# EasyEDA.net
KiCad netlist of a schematic drawn in EasyEDA
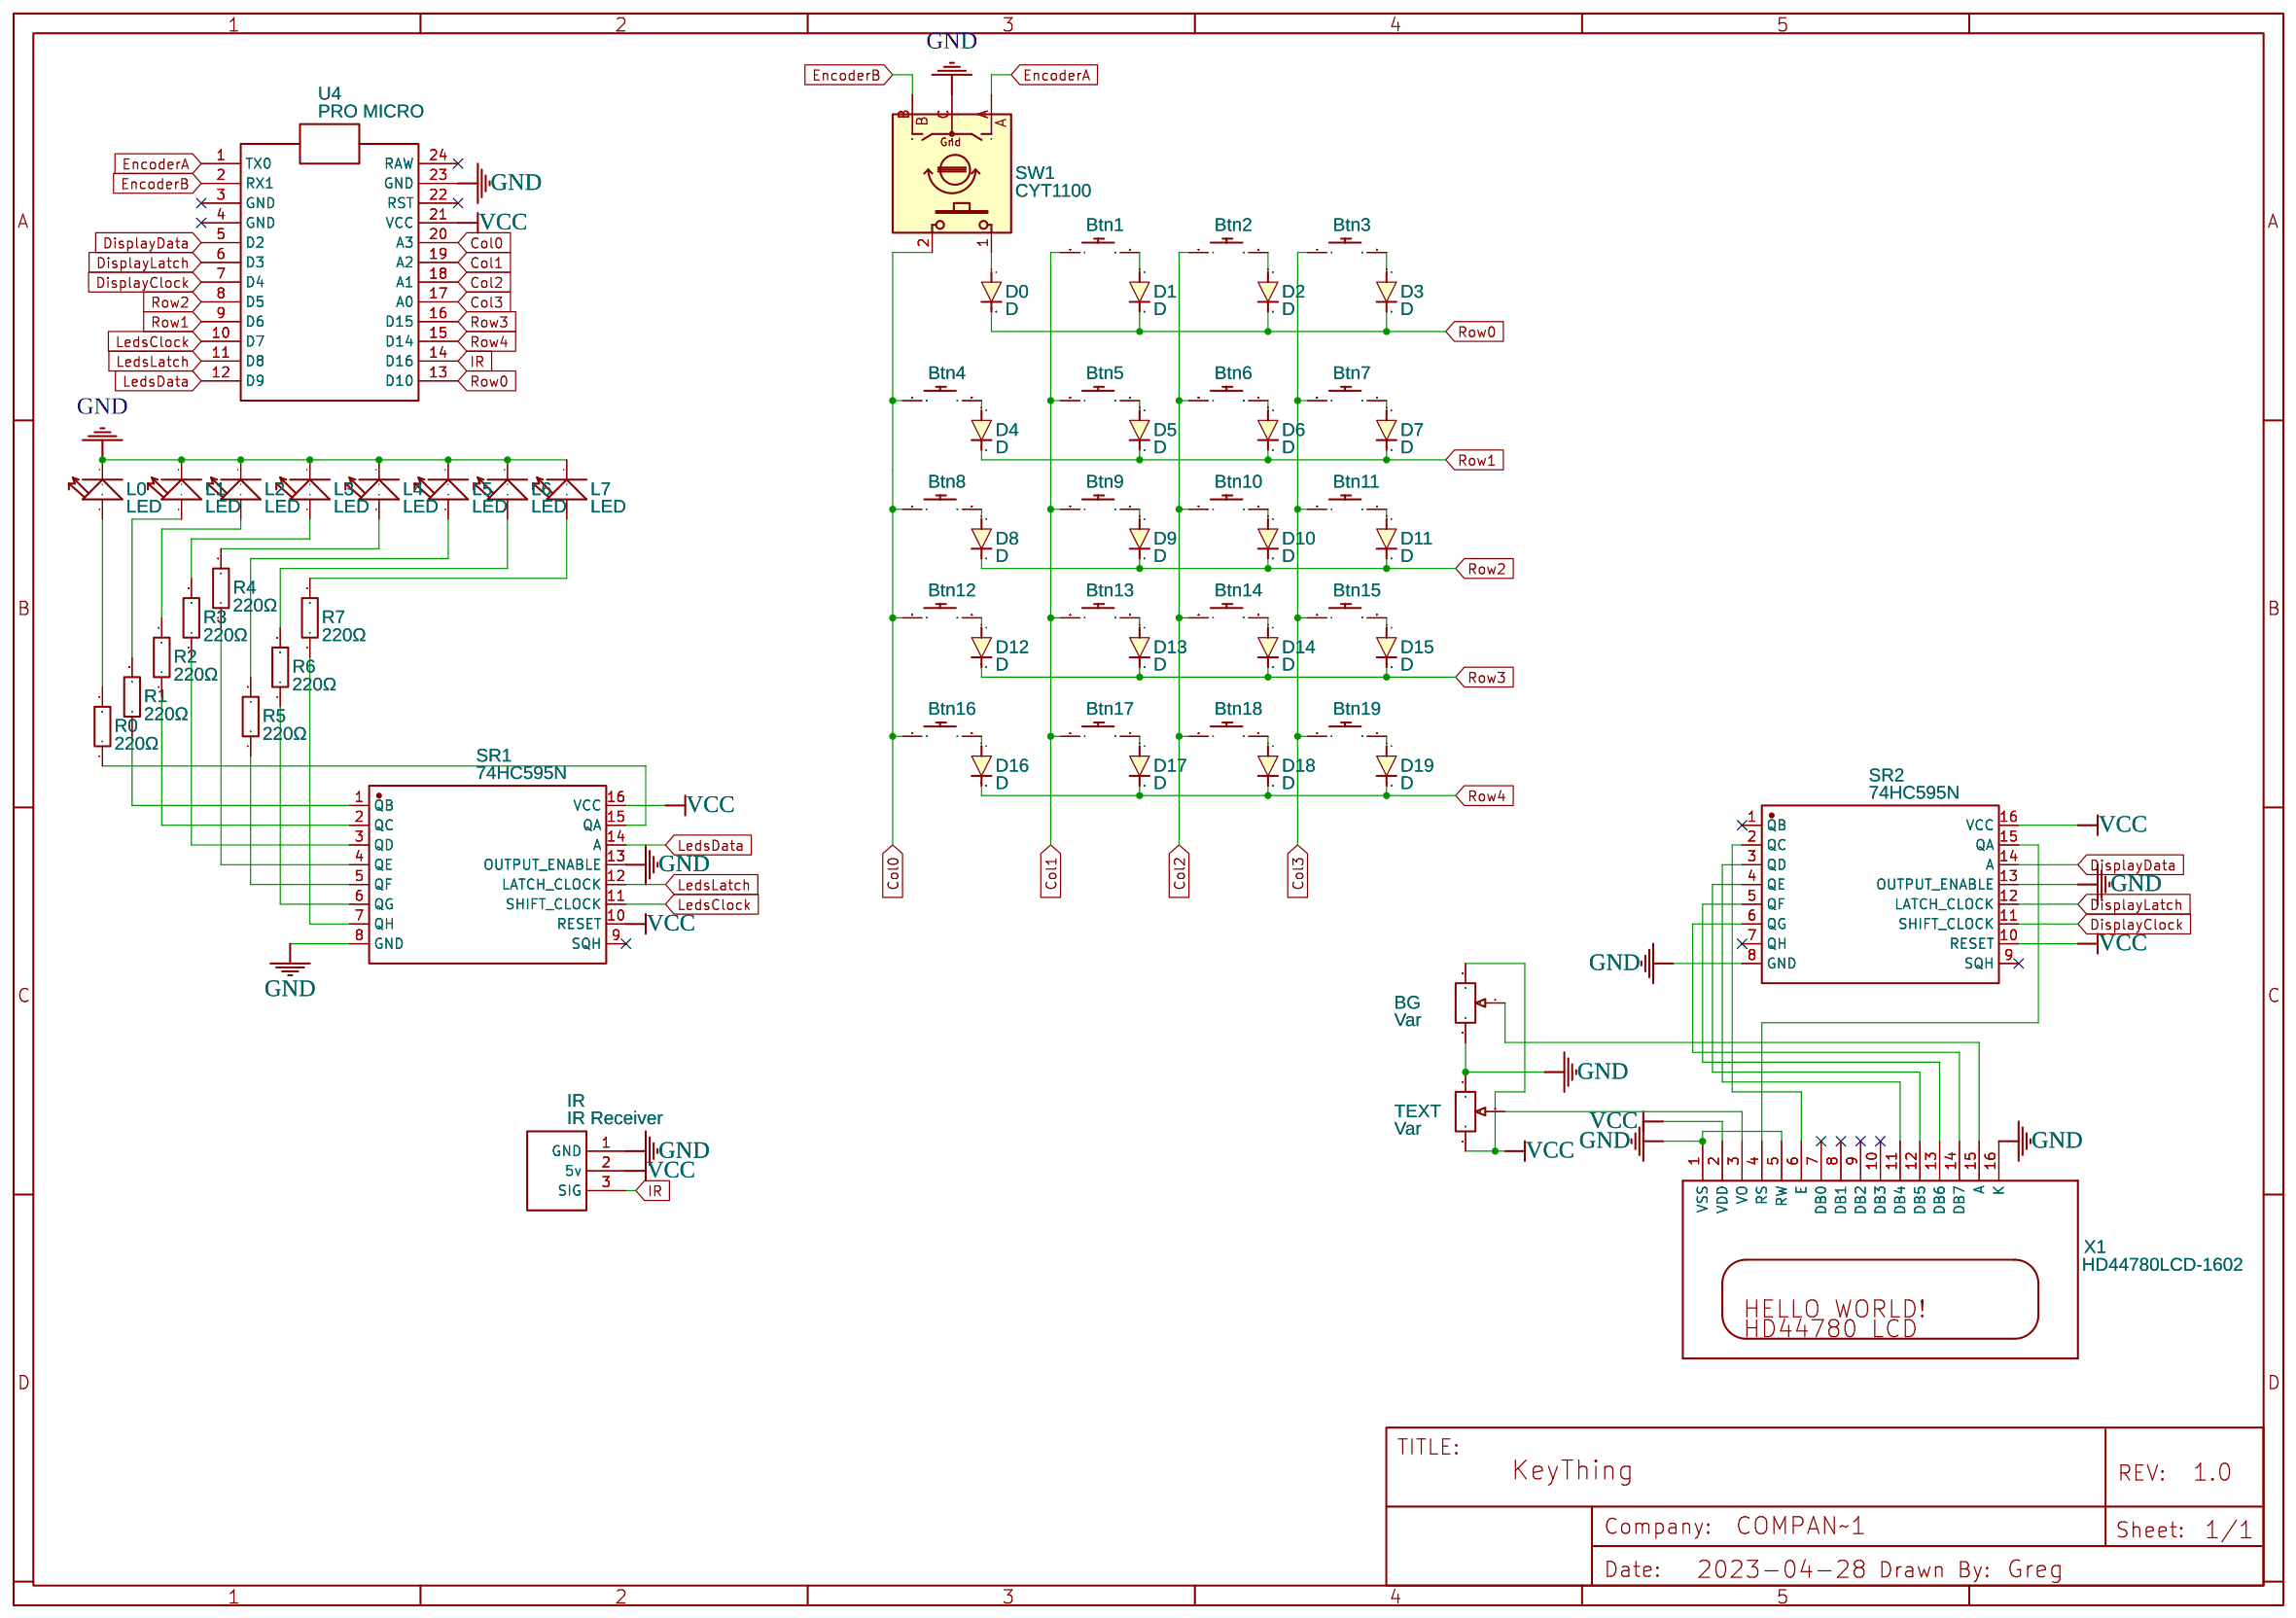
[diagram p0: schematic sheet]

(export (version "E")
  (design (tool "Eeschema 10.0.6"))
  (components
    (comp (ref "B1")
      (value "Btn1")
      (fields (field (name "BOM_Supplier Part") "264546125050"))
      (libsource (lib "") (part "Cherry MX"))
    )
    (comp (ref "B2")
      (value "Btn2")
      (fields (field (name "BOM_Supplier Part") "264546125050"))
      (libsource (lib "") (part "Cherry MX"))
    )
    (comp (ref "B3")
      (value "Btn3")
      (fields (field (name "BOM_Supplier Part") "264546125050"))
      (libsource (lib "") (part "Cherry MX"))
    )
    (comp (ref "B4")
      (value "Btn4")
      (fields (field (name "BOM_Supplier Part") "264546125050"))
      (libsource (lib "") (part "Cherry MX"))
    )
    (comp (ref "B5")
      (value "Btn5")
      (fields (field (name "BOM_Supplier Part") "264546125050"))
      (libsource (lib "") (part "Cherry MX"))
    )
    (comp (ref "B6")
      (value "Btn6")
      (fields (field (name "BOM_Supplier Part") "264546125050"))
      (libsource (lib "") (part "Cherry MX"))
    )
    (comp (ref "B7")
      (value "Btn7")
      (fields (field (name "BOM_Supplier Part") "264546125050"))
      (libsource (lib "") (part "Cherry MX"))
    )
    (comp (ref "B8")
      (value "Btn8")
      (fields (field (name "BOM_Supplier Part") "264546125050"))
      (libsource (lib "") (part "Cherry MX"))
    )
    (comp (ref "B9")
      (value "Btn9")
      (fields (field (name "BOM_Supplier Part") "264546125050"))
      (libsource (lib "") (part "Cherry MX"))
    )
    (comp (ref "B10")
      (value "Btn10")
      (fields (field (name "BOM_Supplier Part") "264546125050"))
      (libsource (lib "") (part "Cherry MX"))
    )
    (comp (ref "B11")
      (value "Btn11")
      (fields (field (name "BOM_Supplier Part") "264546125050"))
      (libsource (lib "") (part "Cherry MX"))
    )
    (comp (ref "B12")
      (value "Btn12")
      (fields (field (name "BOM_Supplier Part") "264546125050"))
      (libsource (lib "") (part "Cherry MX"))
    )
    (comp (ref "B13")
      (value "Btn13")
      (fields (field (name "BOM_Supplier Part") "264546125050"))
      (libsource (lib "") (part "Cherry MX"))
    )
    (comp (ref "B14")
      (value "Btn14")
      (fields (field (name "BOM_Supplier Part") "264546125050"))
      (libsource (lib "") (part "Cherry MX"))
    )
    (comp (ref "B15")
      (value "Btn15")
      (fields (field (name "BOM_Supplier Part") "264546125050"))
      (libsource (lib "") (part "Cherry MX"))
    )
    (comp (ref "B16")
      (value "Btn16")
      (fields (field (name "BOM_Supplier Part") "264546125050"))
      (libsource (lib "") (part "Cherry MX"))
    )
    (comp (ref "B17")
      (value "Btn17")
      (fields (field (name "BOM_Supplier Part") "264546125050"))
      (libsource (lib "") (part "Cherry MX"))
    )
    (comp (ref "B18")
      (value "Btn18")
      (fields (field (name "BOM_Supplier Part") "264546125050"))
      (libsource (lib "") (part "Cherry MX"))
    )
    (comp (ref "B19")
      (value "Btn19")
      (fields (field (name "BOM_Supplier Part") "264546125050"))
      (libsource (lib "") (part "Cherry MX"))
    )
    (comp (ref "BG") (value "Var") (libsource (lib "") (part "R_3386P_EU_1")))
    (comp (ref "D0") (value "D") (libsource (lib "") (part "DIODE-1N4148")))
    (comp (ref "D1") (value "D") (libsource (lib "") (part "DIODE-1N4148")))
    (comp (ref "D2") (value "D") (libsource (lib "") (part "DIODE-1N4148")))
    (comp (ref "D3") (value "D") (libsource (lib "") (part "DIODE-1N4148")))
    (comp (ref "D4") (value "D") (libsource (lib "") (part "DIODE-1N4148")))
    (comp (ref "D5") (value "D") (libsource (lib "") (part "DIODE-1N4148")))
    (comp (ref "D6") (value "D") (libsource (lib "") (part "DIODE-1N4148")))
    (comp (ref "D7") (value "D") (libsource (lib "") (part "DIODE-1N4148")))
    (comp (ref "D8") (value "D") (libsource (lib "") (part "DIODE-1N4148")))
    (comp (ref "D9") (value "D") (libsource (lib "") (part "DIODE-1N4148")))
    (comp (ref "D10") (value "D") (libsource (lib "") (part "DIODE-1N4148")))
    (comp (ref "D11") (value "D") (libsource (lib "") (part "DIODE-1N4148")))
    (comp (ref "D12") (value "D") (libsource (lib "") (part "DIODE-1N4148")))
    (comp (ref "D13") (value "D") (libsource (lib "") (part "DIODE-1N4148")))
    (comp (ref "D14") (value "D") (libsource (lib "") (part "DIODE-1N4148")))
    (comp (ref "D15") (value "D") (libsource (lib "") (part "DIODE-1N4148")))
    (comp (ref "D16") (value "D") (libsource (lib "") (part "DIODE-1N4148")))
    (comp (ref "D17") (value "D") (libsource (lib "") (part "DIODE-1N4148")))
    (comp (ref "D18") (value "D") (libsource (lib "") (part "DIODE-1N4148")))
    (comp (ref "D19") (value "D") (libsource (lib "") (part "DIODE-1N4148")))
    (comp (ref "IR") (value "IR Receiver") (libsource (lib "") (part "IR Receiver")))
    (comp (ref "L0")
      (value "LED")
      (fields (field (name "BOM_Manufacturer Part") "503UOC"))
      (libsource (lib "") (part "503UOC"))
    )
    (comp (ref "L1")
      (value "LED")
      (fields (field (name "BOM_Manufacturer Part") "503UOC"))
      (libsource (lib "") (part "503UOC"))
    )
    (comp (ref "L2")
      (value "LED")
      (fields (field (name "BOM_Manufacturer Part") "503UOC"))
      (libsource (lib "") (part "503UOC"))
    )
    (comp (ref "L3")
      (value "LED")
      (fields (field (name "BOM_Manufacturer Part") "503UOC"))
      (libsource (lib "") (part "503UOC"))
    )
    (comp (ref "L4")
      (value "LED")
      (fields (field (name "BOM_Manufacturer Part") "503UOC"))
      (libsource (lib "") (part "503UOC"))
    )
    (comp (ref "L5")
      (value "LED")
      (fields (field (name "BOM_Manufacturer Part") "503UOC"))
      (libsource (lib "") (part "503UOC"))
    )
    (comp (ref "L6")
      (value "LED")
      (fields (field (name "BOM_Manufacturer Part") "503UOC"))
      (libsource (lib "") (part "503UOC"))
    )
    (comp (ref "L7")
      (value "LED")
      (fields (field (name "BOM_Manufacturer Part") "503UOC"))
      (libsource (lib "") (part "503UOC"))
    )
    (comp (ref "R0")
      (value "220Ω")
      (fields
        (field (name "BOM_Manufacturer Part") "MF1/8W-220Ω±1%-ST52")
        (field (name "BOM_Supplier Part") "C2848572")
      )
      (libsource (lib "") (part "MF1/8W-220Ω±1%-ST52"))
    )
    (comp (ref "R1")
      (value "220Ω")
      (fields
        (field (name "BOM_Manufacturer Part") "MF1/8W-220Ω±1%-ST52")
        (field (name "BOM_Supplier Part") "C2848572")
      )
      (libsource (lib "") (part "MF1/8W-220Ω±1%-ST52"))
    )
    (comp (ref "R2")
      (value "220Ω")
      (fields
        (field (name "BOM_Manufacturer Part") "MF1/8W-220Ω±1%-ST52")
        (field (name "BOM_Supplier Part") "C2848572")
      )
      (libsource (lib "") (part "MF1/8W-220Ω±1%-ST52"))
    )
    (comp (ref "R3")
      (value "220Ω")
      (fields
        (field (name "BOM_Manufacturer Part") "MF1/8W-220Ω±1%-ST52")
        (field (name "BOM_Supplier Part") "C2848572")
      )
      (libsource (lib "") (part "MF1/8W-220Ω±1%-ST52"))
    )
    (comp (ref "R4")
      (value "220Ω")
      (fields
        (field (name "BOM_Manufacturer Part") "MF1/8W-220Ω±1%-ST52")
        (field (name "BOM_Supplier Part") "C2848572")
      )
      (libsource (lib "") (part "MF1/8W-220Ω±1%-ST52"))
    )
    (comp (ref "R5")
      (value "220Ω")
      (fields
        (field (name "BOM_Manufacturer Part") "MF1/8W-220Ω±1%-ST52")
        (field (name "BOM_Supplier Part") "C2848572")
      )
      (libsource (lib "") (part "MF1/8W-220Ω±1%-ST52"))
    )
    (comp (ref "R6")
      (value "220Ω")
      (fields
        (field (name "BOM_Manufacturer Part") "MF1/8W-220Ω±1%-ST52")
        (field (name "BOM_Supplier Part") "C2848572")
      )
      (libsource (lib "") (part "MF1/8W-220Ω±1%-ST52"))
    )
    (comp (ref "R7")
      (value "220Ω")
      (fields
        (field (name "BOM_Manufacturer Part") "MF1/8W-220Ω±1%-ST52")
        (field (name "BOM_Supplier Part") "C2848572")
      )
      (libsource (lib "") (part "MF1/8W-220Ω±1%-ST52"))
    )
    (comp (ref "SR1")
      (value "74HC595N")
      (fields (field (name "BOM_Supplier Part") "C507175"))
      (libsource (lib "") (part "74HC595N"))
    )
    (comp (ref "SR2")
      (value "74HC595N")
      (fields (field (name "BOM_Supplier Part") "C507175"))
      (libsource (lib "") (part "74HC595N"))
    )
    (comp (ref "SW1")
      (value "CYT1100")
      (fields
        (field (name "BOM_Manufacturer Part") "PEC11R-4015F-S0024")
        (field (name "BOM_Supplier Part") "C143789")
      )
      (libsource (lib "") (part "CYT1100"))
    )
    (comp (ref "TEXT") (value "Var") (libsource (lib "") (part "R_3386P_EU")))
    (comp (ref "U4") (value "PRO MICRO") (libsource (lib "") (part "PRO MICRO")))
    (comp (ref "X1") (value "HD44780LCD-1602") (libsource (lib "") (part "HD44780LCD-1602")))
  )
  (nets
    (net (code "1") (name "Col0") (class "Default")
      (node (ref "B12") (pin "S1") (pinfunction "1_S1") (pintype "bidirectional"))
      (node (ref "B16") (pin "S1") (pinfunction "1_S1") (pintype "bidirectional"))
      (node (ref "B4") (pin "S1") (pinfunction "1_S1") (pintype "bidirectional"))
      (node (ref "B8") (pin "S1") (pinfunction "1_S1") (pintype "bidirectional"))
      (node (ref "SW1") (pin "2") (pinfunction "2_2") (pintype "unspecified"))
      (node (ref "U4") (pin "20") (pinfunction "A3_20") (pintype "unspecified"))
    )
    (net (code "2") (name "Col1") (class "Default")
      (node (ref "B1") (pin "S1") (pinfunction "1_S1") (pintype "bidirectional"))
      (node (ref "B13") (pin "S1") (pinfunction "1_S1") (pintype "bidirectional"))
      (node (ref "B17") (pin "S1") (pinfunction "1_S1") (pintype "bidirectional"))
      (node (ref "B5") (pin "S1") (pinfunction "1_S1") (pintype "bidirectional"))
      (node (ref "B9") (pin "S1") (pinfunction "1_S1") (pintype "bidirectional"))
      (node (ref "U4") (pin "19") (pinfunction "A2_19") (pintype "unspecified"))
    )
    (net (code "3") (name "Col2") (class "Default")
      (node (ref "B10") (pin "S1") (pinfunction "1_S1") (pintype "bidirectional"))
      (node (ref "B14") (pin "S1") (pinfunction "1_S1") (pintype "bidirectional"))
      (node (ref "B18") (pin "S1") (pinfunction "1_S1") (pintype "bidirectional"))
      (node (ref "B2") (pin "S1") (pinfunction "1_S1") (pintype "bidirectional"))
      (node (ref "B6") (pin "S1") (pinfunction "1_S1") (pintype "bidirectional"))
      (node (ref "U4") (pin "18") (pinfunction "A1_18") (pintype "unspecified"))
    )
    (net (code "4") (name "Col3") (class "Default")
      (node (ref "B11") (pin "S1") (pinfunction "1_S1") (pintype "bidirectional"))
      (node (ref "B15") (pin "S1") (pinfunction "1_S1") (pintype "bidirectional"))
      (node (ref "B19") (pin "S1") (pinfunction "1_S1") (pintype "bidirectional"))
      (node (ref "B3") (pin "S1") (pinfunction "1_S1") (pintype "bidirectional"))
      (node (ref "B7") (pin "S1") (pinfunction "1_S1") (pintype "bidirectional"))
      (node (ref "U4") (pin "17") (pinfunction "A0_17") (pintype "unspecified"))
    )
    (net (code "5") (name "DisplayClock") (class "Default")
      (node (ref "SR2") (pin "11") (pinfunction "SHIFT_CLOCK_11") (pintype "unspecified"))
      (node (ref "U4") (pin "7") (pinfunction "D4_7") (pintype "unspecified"))
    )
    (net (code "6") (name "DisplayData") (class "Default")
      (node (ref "SR2") (pin "14") (pinfunction "A_14") (pintype "unspecified"))
      (node (ref "U4") (pin "5") (pinfunction "D2_5") (pintype "unspecified"))
    )
    (net (code "7") (name "DisplayLatch") (class "Default")
      (node (ref "SR2") (pin "12") (pinfunction "LATCH_CLOCK_12") (pintype "unspecified"))
      (node (ref "U4") (pin "6") (pinfunction "D3_6") (pintype "unspecified"))
    )
    (net (code "8") (name "EncoderA") (class "Default")
      (node (ref "SW1") (pin "A") (pinfunction "A_A") (pintype "unspecified"))
      (node (ref "U4") (pin "1") (pinfunction "TX0_1") (pintype "unspecified"))
    )
    (net (code "9") (name "EncoderB") (class "Default")
      (node (ref "SW1") (pin "B") (pinfunction "B_B") (pintype "unspecified"))
      (node (ref "U4") (pin "2") (pinfunction "RX1_2") (pintype "unspecified"))
    )
    (net (code "10") (name "GND") (class "Default")
      (node (ref "BG") (pin "3") (pinfunction "3_3") (pintype "input"))
      (node (ref "IR") (pin "1") (pinfunction "GND_1") (pintype "unspecified"))
      (node (ref "L0") (pin "-") (pinfunction "-_-") (pintype "unspecified"))
      (node (ref "L1") (pin "-") (pinfunction "-_-") (pintype "unspecified"))
      (node (ref "L2") (pin "-") (pinfunction "-_-") (pintype "unspecified"))
      (node (ref "L3") (pin "-") (pinfunction "-_-") (pintype "unspecified"))
      (node (ref "L4") (pin "-") (pinfunction "-_-") (pintype "unspecified"))
      (node (ref "L5") (pin "-") (pinfunction "-_-") (pintype "unspecified"))
      (node (ref "L6") (pin "-") (pinfunction "-_-") (pintype "unspecified"))
      (node (ref "L7") (pin "-") (pinfunction "-_-") (pintype "unspecified"))
      (node (ref "SR1") (pin "13") (pinfunction "OUTPUT_ENABLE_13") (pintype "unspecified"))
      (node (ref "SR1") (pin "8") (pinfunction "GND_8") (pintype "unspecified"))
      (node (ref "SR2") (pin "13") (pinfunction "OUTPUT_ENABLE_13") (pintype "unspecified"))
      (node (ref "SR2") (pin "8") (pinfunction "GND_8") (pintype "unspecified"))
      (node (ref "SW1") (pin "C") (pinfunction "C_C") (pintype "unspecified"))
      (node (ref "TEXT") (pin "1") (pinfunction "1_1") (pintype "input"))
      (node (ref "U4") (pin "23") (pinfunction "GND_23") (pintype "unspecified"))
      (node (ref "X1") (pin "1") (pinfunction "VSS_1") (pintype "unspecified"))
      (node (ref "X1") (pin "16") (pinfunction "K_16") (pintype "input"))
      (node (ref "X1") (pin "5") (pinfunction "RW_5") (pintype "input"))
    )
    (net (code "11") (name "IR") (class "Default")
      (node (ref "IR") (pin "3") (pinfunction "SIG_3") (pintype "unspecified"))
      (node (ref "U4") (pin "14") (pinfunction "D16_14") (pintype "unspecified"))
    )
    (net (code "12") (name "LedsClock") (class "Default")
      (node (ref "SR1") (pin "11") (pinfunction "SHIFT_CLOCK_11") (pintype "unspecified"))
      (node (ref "U4") (pin "10") (pinfunction "D7_10") (pintype "unspecified"))
    )
    (net (code "13") (name "LedsData") (class "Default")
      (node (ref "SR1") (pin "14") (pinfunction "A_14") (pintype "unspecified"))
      (node (ref "U4") (pin "12") (pinfunction "D9_12") (pintype "unspecified"))
    )
    (net (code "14") (name "LedsLatch") (class "Default")
      (node (ref "SR1") (pin "12") (pinfunction "LATCH_CLOCK_12") (pintype "unspecified"))
      (node (ref "U4") (pin "11") (pinfunction "D8_11") (pintype "unspecified"))
    )
    (net (code "15") (name "Net-(B1-2)") (class "Default")
      (node (ref "B1") (pin "S2") (pinfunction "2_S2") (pintype "bidirectional"))
      (node (ref "D1") (pin "A") (pinfunction "A_A") (pintype "bidirectional"))
    )
    (net (code "16") (name "Net-(B2-2)") (class "Default")
      (node (ref "B2") (pin "S2") (pinfunction "2_S2") (pintype "bidirectional"))
      (node (ref "D2") (pin "A") (pinfunction "A_A") (pintype "bidirectional"))
    )
    (net (code "17") (name "Net-(B3-2)") (class "Default")
      (node (ref "B3") (pin "S2") (pinfunction "2_S2") (pintype "bidirectional"))
      (node (ref "D3") (pin "A") (pinfunction "A_A") (pintype "bidirectional"))
    )
    (net (code "18") (name "Net-(B4-2)") (class "Default")
      (node (ref "B4") (pin "S2") (pinfunction "2_S2") (pintype "bidirectional"))
      (node (ref "D4") (pin "A") (pinfunction "A_A") (pintype "bidirectional"))
    )
    (net (code "19") (name "Net-(B5-2)") (class "Default")
      (node (ref "B5") (pin "S2") (pinfunction "2_S2") (pintype "bidirectional"))
      (node (ref "D5") (pin "A") (pinfunction "A_A") (pintype "bidirectional"))
    )
    (net (code "20") (name "Net-(B6-2)") (class "Default")
      (node (ref "B6") (pin "S2") (pinfunction "2_S2") (pintype "bidirectional"))
      (node (ref "D6") (pin "A") (pinfunction "A_A") (pintype "bidirectional"))
    )
    (net (code "21") (name "Net-(B7-2)") (class "Default")
      (node (ref "B7") (pin "S2") (pinfunction "2_S2") (pintype "bidirectional"))
      (node (ref "D7") (pin "A") (pinfunction "A_A") (pintype "bidirectional"))
    )
    (net (code "22") (name "Net-(B8-2)") (class "Default")
      (node (ref "B8") (pin "S2") (pinfunction "2_S2") (pintype "bidirectional"))
      (node (ref "D8") (pin "A") (pinfunction "A_A") (pintype "bidirectional"))
    )
    (net (code "23") (name "Net-(B9-2)") (class "Default")
      (node (ref "B9") (pin "S2") (pinfunction "2_S2") (pintype "bidirectional"))
      (node (ref "D9") (pin "A") (pinfunction "A_A") (pintype "bidirectional"))
    )
    (net (code "24") (name "Net-(B10-2)") (class "Default")
      (node (ref "B10") (pin "S2") (pinfunction "2_S2") (pintype "bidirectional"))
      (node (ref "D10") (pin "A") (pinfunction "A_A") (pintype "bidirectional"))
    )
    (net (code "25") (name "Net-(B11-2)") (class "Default")
      (node (ref "B11") (pin "S2") (pinfunction "2_S2") (pintype "bidirectional"))
      (node (ref "D11") (pin "A") (pinfunction "A_A") (pintype "bidirectional"))
    )
    (net (code "26") (name "Net-(B12-2)") (class "Default")
      (node (ref "B12") (pin "S2") (pinfunction "2_S2") (pintype "bidirectional"))
      (node (ref "D12") (pin "A") (pinfunction "A_A") (pintype "bidirectional"))
    )
    (net (code "27") (name "Net-(B13-2)") (class "Default")
      (node (ref "B13") (pin "S2") (pinfunction "2_S2") (pintype "bidirectional"))
      (node (ref "D13") (pin "A") (pinfunction "A_A") (pintype "bidirectional"))
    )
    (net (code "28") (name "Net-(B14-2)") (class "Default")
      (node (ref "B14") (pin "S2") (pinfunction "2_S2") (pintype "bidirectional"))
      (node (ref "D14") (pin "A") (pinfunction "A_A") (pintype "bidirectional"))
    )
    (net (code "29") (name "Net-(B15-2)") (class "Default")
      (node (ref "B15") (pin "S2") (pinfunction "2_S2") (pintype "bidirectional"))
      (node (ref "D15") (pin "A") (pinfunction "A_A") (pintype "bidirectional"))
    )
    (net (code "30") (name "Net-(B16-2)") (class "Default")
      (node (ref "B16") (pin "S2") (pinfunction "2_S2") (pintype "bidirectional"))
      (node (ref "D16") (pin "A") (pinfunction "A_A") (pintype "bidirectional"))
    )
    (net (code "31") (name "Net-(B17-2)") (class "Default")
      (node (ref "B17") (pin "S2") (pinfunction "2_S2") (pintype "bidirectional"))
      (node (ref "D17") (pin "A") (pinfunction "A_A") (pintype "bidirectional"))
    )
    (net (code "32") (name "Net-(B18-2)") (class "Default")
      (node (ref "B18") (pin "S2") (pinfunction "2_S2") (pintype "bidirectional"))
      (node (ref "D18") (pin "A") (pinfunction "A_A") (pintype "bidirectional"))
    )
    (net (code "33") (name "Net-(B19-2)") (class "Default")
      (node (ref "B19") (pin "S2") (pinfunction "2_S2") (pintype "bidirectional"))
      (node (ref "D19") (pin "A") (pinfunction "A_A") (pintype "bidirectional"))
    )
    (net (code "34") (name "Net-(D0-PadA)") (class "Default")
      (node (ref "D0") (pin "A") (pinfunction "A_A") (pintype "bidirectional"))
      (node (ref "SW1") (pin "1") (pinfunction "1_1") (pintype "unspecified"))
    )
    (net (code "35") (name "Net-(L0-Pad+)") (class "Default")
      (node (ref "L0") (pin "+") (pinfunction "+_+") (pintype "unspecified"))
      (node (ref "R0") (pin "2") (pinfunction "2_2") (pintype "unspecified"))
    )
    (net (code "36") (name "Net-(L1-Pad+)") (class "Default")
      (node (ref "L1") (pin "+") (pinfunction "+_+") (pintype "unspecified"))
      (node (ref "R1") (pin "2") (pinfunction "2_2") (pintype "unspecified"))
    )
    (net (code "37") (name "Net-(L2-Pad+)") (class "Default")
      (node (ref "L2") (pin "+") (pinfunction "+_+") (pintype "unspecified"))
      (node (ref "R2") (pin "2") (pinfunction "2_2") (pintype "unspecified"))
    )
    (net (code "38") (name "Net-(L3-Pad+)") (class "Default")
      (node (ref "L3") (pin "+") (pinfunction "+_+") (pintype "unspecified"))
      (node (ref "R3") (pin "2") (pinfunction "2_2") (pintype "unspecified"))
    )
    (net (code "39") (name "Net-(L4-Pad+)") (class "Default")
      (node (ref "L4") (pin "+") (pinfunction "+_+") (pintype "unspecified"))
      (node (ref "R4") (pin "2") (pinfunction "2_2") (pintype "unspecified"))
    )
    (net (code "40") (name "Net-(L5-Pad+)") (class "Default")
      (node (ref "L5") (pin "+") (pinfunction "+_+") (pintype "unspecified"))
      (node (ref "R5") (pin "2") (pinfunction "2_2") (pintype "unspecified"))
    )
    (net (code "41") (name "Net-(L6-Pad+)") (class "Default")
      (node (ref "L6") (pin "+") (pinfunction "+_+") (pintype "unspecified"))
      (node (ref "R6") (pin "2") (pinfunction "2_2") (pintype "unspecified"))
    )
    (net (code "42") (name "Net-(L7-Pad+)") (class "Default")
      (node (ref "L7") (pin "+") (pinfunction "+_+") (pintype "unspecified"))
      (node (ref "R7") (pin "2") (pinfunction "2_2") (pintype "unspecified"))
    )
    (net (code "43") (name "Net-(SR1-QA)") (class "Default")
      (node (ref "R0") (pin "1") (pinfunction "1_1") (pintype "unspecified"))
      (node (ref "SR1") (pin "15") (pinfunction "QA_15") (pintype "unspecified"))
    )
    (net (code "44") (name "Net-(SR1-QB)") (class "Default")
      (node (ref "R1") (pin "1") (pinfunction "1_1") (pintype "unspecified"))
      (node (ref "SR1") (pin "1") (pinfunction "QB_1") (pintype "unspecified"))
    )
    (net (code "45") (name "Net-(SR1-QC)") (class "Default")
      (node (ref "R2") (pin "1") (pinfunction "1_1") (pintype "unspecified"))
      (node (ref "SR1") (pin "2") (pinfunction "QC_2") (pintype "unspecified"))
    )
    (net (code "46") (name "Net-(SR1-QD)") (class "Default")
      (node (ref "R3") (pin "1") (pinfunction "1_1") (pintype "unspecified"))
      (node (ref "SR1") (pin "3") (pinfunction "QD_3") (pintype "unspecified"))
    )
    (net (code "47") (name "Net-(SR1-QE)") (class "Default")
      (node (ref "R4") (pin "1") (pinfunction "1_1") (pintype "unspecified"))
      (node (ref "SR1") (pin "4") (pinfunction "QE_4") (pintype "unspecified"))
    )
    (net (code "48") (name "Net-(SR1-QF)") (class "Default")
      (node (ref "R5") (pin "1") (pinfunction "1_1") (pintype "unspecified"))
      (node (ref "SR1") (pin "5") (pinfunction "QF_5") (pintype "unspecified"))
    )
    (net (code "49") (name "Net-(SR1-QG)") (class "Default")
      (node (ref "R6") (pin "1") (pinfunction "1_1") (pintype "unspecified"))
      (node (ref "SR1") (pin "6") (pinfunction "QG_6") (pintype "unspecified"))
    )
    (net (code "50") (name "Net-(SR1-QH)") (class "Default")
      (node (ref "R7") (pin "1") (pinfunction "1_1") (pintype "unspecified"))
      (node (ref "SR1") (pin "7") (pinfunction "QH_7") (pintype "unspecified"))
    )
    (net (code "51") (name "Net-(SR2-QA)") (class "Default")
      (node (ref "SR2") (pin "15") (pinfunction "QA_15") (pintype "unspecified"))
      (node (ref "X1") (pin "4") (pinfunction "RS_4") (pintype "input"))
    )
    (net (code "52") (name "Net-(SR2-QC)") (class "Default")
      (node (ref "SR2") (pin "2") (pinfunction "QC_2") (pintype "unspecified"))
      (node (ref "X1") (pin "6") (pinfunction "E_6") (pintype "input"))
    )
    (net (code "53") (name "Net-(SR2-QD)") (class "Default")
      (node (ref "SR2") (pin "3") (pinfunction "QD_3") (pintype "unspecified"))
      (node (ref "X1") (pin "11") (pinfunction "DB4_11") (pintype "unspecified"))
    )
    (net (code "54") (name "Net-(SR2-QE)") (class "Default")
      (node (ref "SR2") (pin "4") (pinfunction "QE_4") (pintype "unspecified"))
      (node (ref "X1") (pin "12") (pinfunction "DB5_12") (pintype "unspecified"))
    )
    (net (code "55") (name "Net-(SR2-QF)") (class "Default")
      (node (ref "SR2") (pin "5") (pinfunction "QF_5") (pintype "unspecified"))
      (node (ref "X1") (pin "13") (pinfunction "DB6_13") (pintype "unspecified"))
    )
    (net (code "56") (name "Net-(SR2-QG)") (class "Default")
      (node (ref "SR2") (pin "6") (pinfunction "QG_6") (pintype "unspecified"))
      (node (ref "X1") (pin "14") (pinfunction "DB7_14") (pintype "unspecified"))
    )
    (net (code "57") (name "Net-(X1-A)") (class "Default")
      (node (ref "BG") (pin "2") (pinfunction "2_2") (pintype "input"))
      (node (ref "X1") (pin "15") (pinfunction "A_15") (pintype "input"))
    )
    (net (code "58") (name "Net-(X1-VO)") (class "Default")
      (node (ref "TEXT") (pin "2") (pinfunction "2_2") (pintype "input"))
      (node (ref "X1") (pin "3") (pinfunction "VO_3") (pintype "input"))
    )
    (net (code "59") (name "Row0") (class "Default")
      (node (ref "D0") (pin "C") (pinfunction "C_C") (pintype "bidirectional"))
      (node (ref "D1") (pin "C") (pinfunction "C_C") (pintype "bidirectional"))
      (node (ref "D2") (pin "C") (pinfunction "C_C") (pintype "bidirectional"))
      (node (ref "D3") (pin "C") (pinfunction "C_C") (pintype "bidirectional"))
      (node (ref "U4") (pin "13") (pinfunction "D10_13") (pintype "unspecified"))
    )
    (net (code "60") (name "Row1") (class "Default")
      (node (ref "D4") (pin "C") (pinfunction "C_C") (pintype "bidirectional"))
      (node (ref "D5") (pin "C") (pinfunction "C_C") (pintype "bidirectional"))
      (node (ref "D6") (pin "C") (pinfunction "C_C") (pintype "bidirectional"))
      (node (ref "D7") (pin "C") (pinfunction "C_C") (pintype "bidirectional"))
      (node (ref "U4") (pin "9") (pinfunction "D6_9") (pintype "unspecified"))
    )
    (net (code "61") (name "Row2") (class "Default")
      (node (ref "D10") (pin "C") (pinfunction "C_C") (pintype "bidirectional"))
      (node (ref "D11") (pin "C") (pinfunction "C_C") (pintype "bidirectional"))
      (node (ref "D8") (pin "C") (pinfunction "C_C") (pintype "bidirectional"))
      (node (ref "D9") (pin "C") (pinfunction "C_C") (pintype "bidirectional"))
      (node (ref "U4") (pin "8") (pinfunction "D5_8") (pintype "unspecified"))
    )
    (net (code "62") (name "Row3") (class "Default")
      (node (ref "D12") (pin "C") (pinfunction "C_C") (pintype "bidirectional"))
      (node (ref "D13") (pin "C") (pinfunction "C_C") (pintype "bidirectional"))
      (node (ref "D14") (pin "C") (pinfunction "C_C") (pintype "bidirectional"))
      (node (ref "D15") (pin "C") (pinfunction "C_C") (pintype "bidirectional"))
      (node (ref "U4") (pin "16") (pinfunction "D15_16") (pintype "unspecified"))
    )
    (net (code "63") (name "Row4") (class "Default")
      (node (ref "D16") (pin "C") (pinfunction "C_C") (pintype "bidirectional"))
      (node (ref "D17") (pin "C") (pinfunction "C_C") (pintype "bidirectional"))
      (node (ref "D18") (pin "C") (pinfunction "C_C") (pintype "bidirectional"))
      (node (ref "D19") (pin "C") (pinfunction "C_C") (pintype "bidirectional"))
      (node (ref "U4") (pin "15") (pinfunction "D14_15") (pintype "unspecified"))
    )
    (net (code "64") (name "VCC") (class "Default")
      (node (ref "BG") (pin "1") (pinfunction "1_1") (pintype "input"))
      (node (ref "IR") (pin "2") (pinfunction "5v_2") (pintype "unspecified"))
      (node (ref "SR1") (pin "10") (pinfunction "RESET_10") (pintype "unspecified"))
      (node (ref "SR1") (pin "16") (pinfunction "VCC_16") (pintype "unspecified"))
      (node (ref "SR2") (pin "10") (pinfunction "RESET_10") (pintype "unspecified"))
      (node (ref "SR2") (pin "16") (pinfunction "VCC_16") (pintype "unspecified"))
      (node (ref "TEXT") (pin "3") (pinfunction "3_3") (pintype "input"))
      (node (ref "U4") (pin "21") (pinfunction "VCC_21") (pintype "unspecified"))
      (node (ref "X1") (pin "2") (pinfunction "VDD_2") (pintype "unspecified"))
    )
    (net (code "65") (name "unconnected-(SR1-SQH-Pad9)") (class "Default")
      (node (ref "SR1") (pin "9") (pinfunction "SQH_9") (pintype "unspecified+no_connect"))
    )
    (net (code "66") (name "unconnected-(SR2-QB-Pad1)") (class "Default")
      (node (ref "SR2") (pin "1") (pinfunction "QB_1") (pintype "unspecified+no_connect"))
    )
    (net (code "67") (name "unconnected-(SR2-QH-Pad7)") (class "Default")
      (node (ref "SR2") (pin "7") (pinfunction "QH_7") (pintype "unspecified+no_connect"))
    )
    (net (code "68") (name "unconnected-(SR2-SQH-Pad9)") (class "Default")
      (node (ref "SR2") (pin "9") (pinfunction "SQH_9") (pintype "unspecified+no_connect"))
    )
    (net (code "69") (name "unconnected-(U4-GND-Pad3)") (class "Default")
      (node (ref "U4") (pin "3") (pinfunction "GND_3") (pintype "unspecified+no_connect"))
    )
    (net (code "70") (name "unconnected-(U4-GND-Pad4)") (class "Default")
      (node (ref "U4") (pin "4") (pinfunction "GND_4") (pintype "unspecified+no_connect"))
    )
    (net (code "71") (name "unconnected-(U4-RAW-Pad24)") (class "Default")
      (node (ref "U4") (pin "24") (pinfunction "RAW_24") (pintype "unspecified+no_connect"))
    )
    (net (code "72") (name "unconnected-(U4-RST-Pad22)") (class "Default")
      (node (ref "U4") (pin "22") (pinfunction "RST_22") (pintype "unspecified+no_connect"))
    )
    (net (code "73") (name "unconnected-(X1-DB0-Pad7)") (class "Default")
      (node (ref "X1") (pin "7") (pinfunction "DB0_7") (pintype "unspecified+no_connect"))
    )
    (net (code "74") (name "unconnected-(X1-DB1-Pad8)") (class "Default")
      (node (ref "X1") (pin "8") (pinfunction "DB1_8") (pintype "unspecified+no_connect"))
    )
    (net (code "75") (name "unconnected-(X1-DB2-Pad9)") (class "Default")
      (node (ref "X1") (pin "9") (pinfunction "DB2_9") (pintype "unspecified+no_connect"))
    )
    (net (code "76") (name "unconnected-(X1-DB3-Pad10)") (class "Default")
      (node (ref "X1") (pin "10") (pinfunction "DB3_10") (pintype "unspecified+no_connect"))
    )
  )
)
